# Display-Board_Rack-PDU_1_0.net
KiCad netlist of a schematic drawn in EAGLE
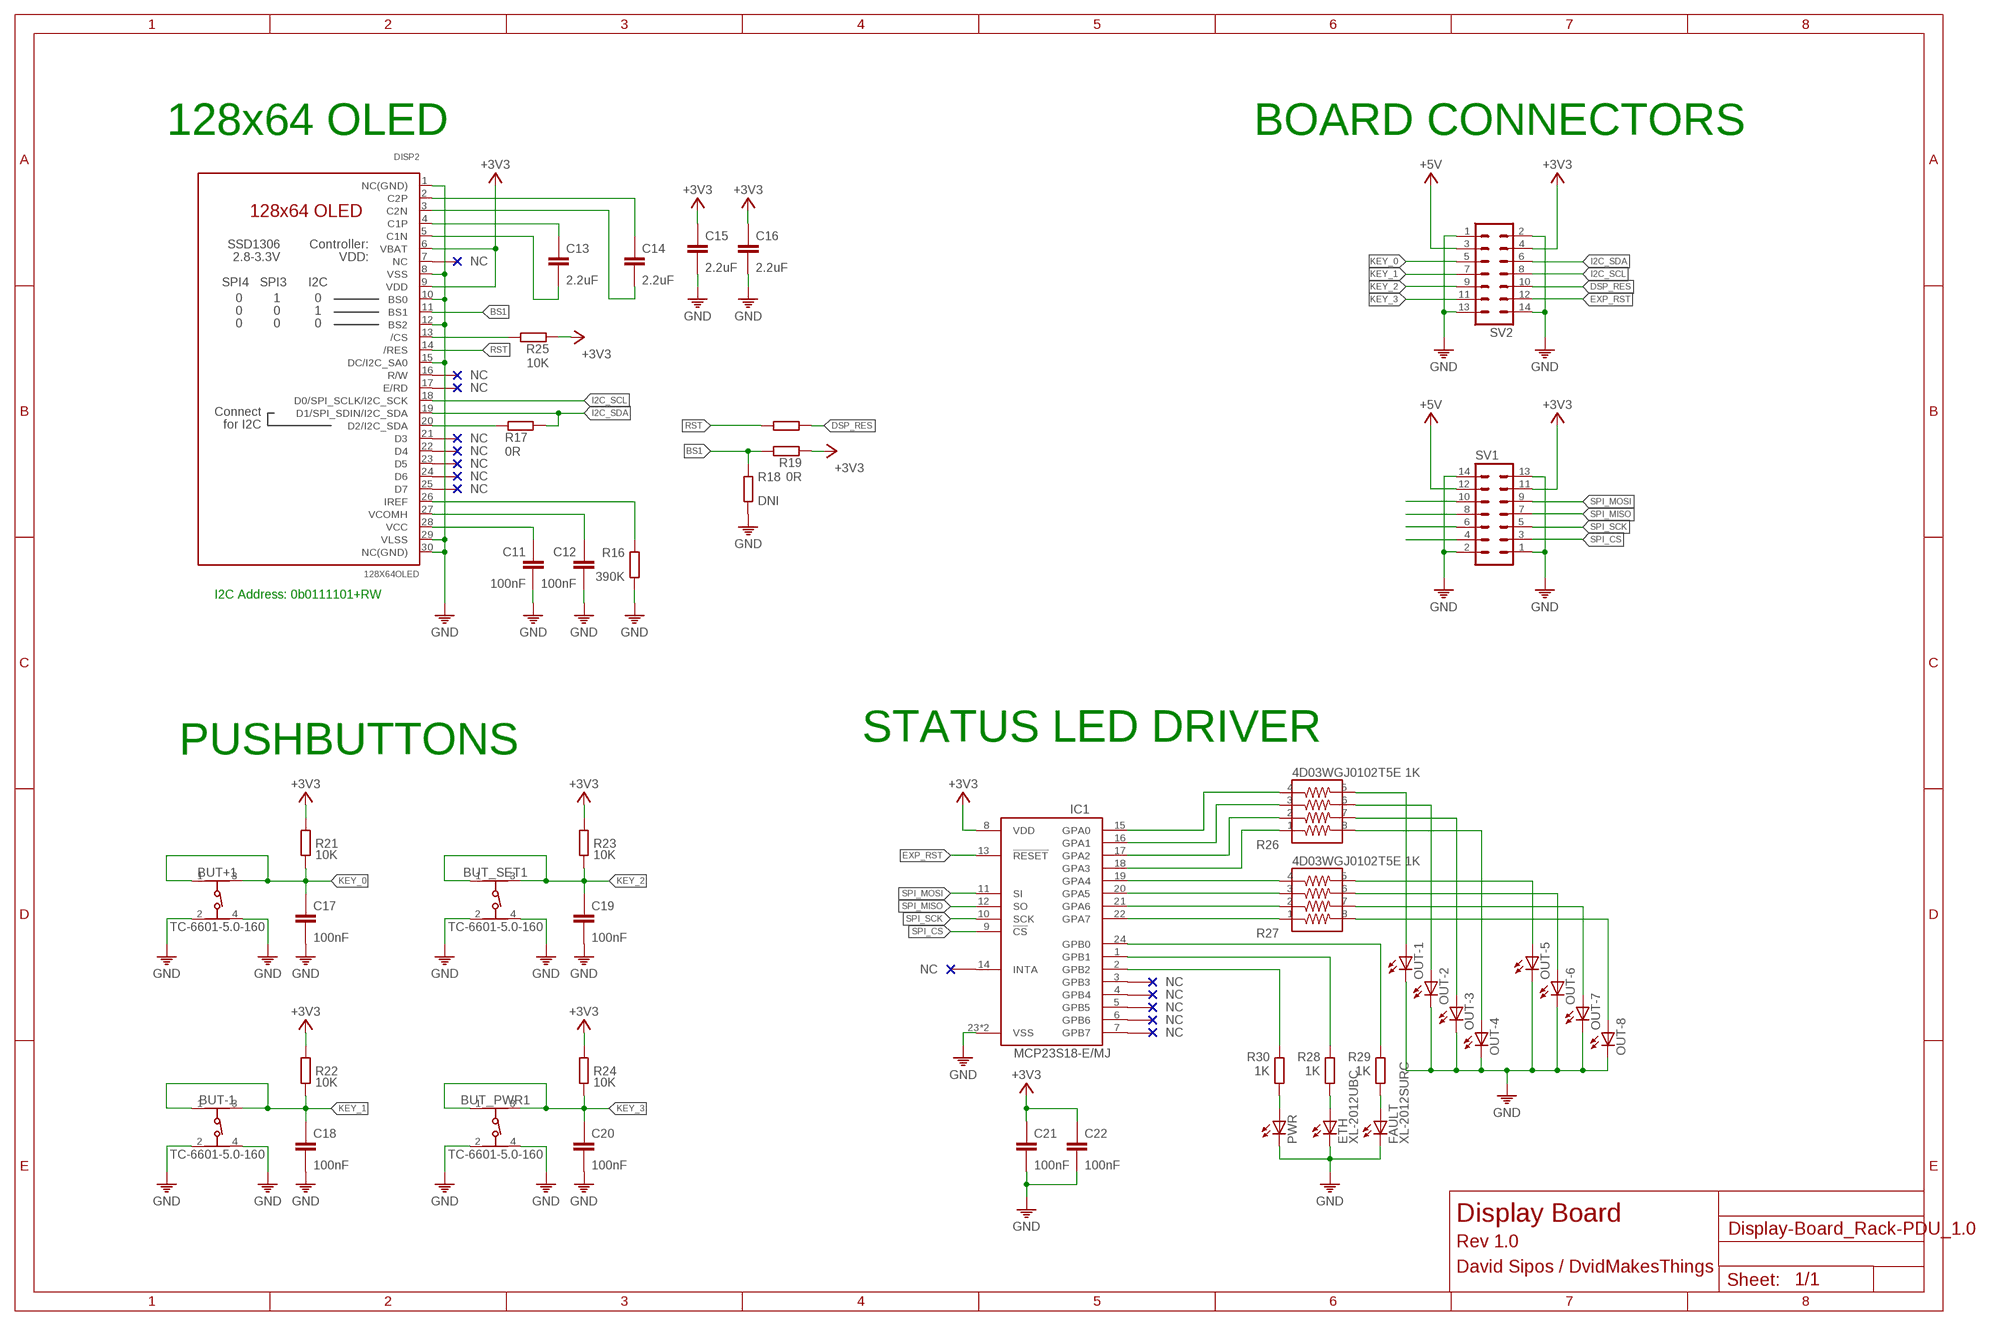
[diagram p0: schematic, sheet 1]

(export (version "E")
  (design (tool "Eeschema 10.0.6"))
  (components
    (comp (ref "BUT+1")
      (value "TC-6601-5.0-160")
      (footprint "eagle-import:430182043816")
      (libsource (lib "eagle-import") (part "430182043816"))
    )
    (comp (ref "BUT-1")
      (value "TC-6601-5.0-160")
      (footprint "eagle-import:430182043816")
      (libsource (lib "eagle-import") (part "430182043816"))
    )
    (comp (ref "BUT_PWR1")
      (value "TC-6601-5.0-160")
      (footprint "eagle-import:430182043816")
      (libsource (lib "eagle-import") (part "430182043816"))
    )
    (comp (ref "BUT_SET1")
      (value "TC-6601-5.0-160")
      (footprint "eagle-import:430182043816")
      (libsource (lib "eagle-import") (part "430182043816"))
    )
    (comp (ref "C11")
      (value "100nF")
      (footprint "eagle-import:0402")
      (libsource (lib "eagle-import") (part "C0402"))
    )
    (comp (ref "C12")
      (value "100nF")
      (footprint "eagle-import:0402")
      (libsource (lib "eagle-import") (part "C0402"))
    )
    (comp (ref "C13")
      (value "2.2uF")
      (footprint "eagle-import:0402")
      (libsource (lib "eagle-import") (part "C0402"))
    )
    (comp (ref "C14")
      (value "2.2uF")
      (footprint "eagle-import:0402")
      (libsource (lib "eagle-import") (part "C0402"))
    )
    (comp (ref "C15")
      (value "2.2uF")
      (footprint "eagle-import:0402")
      (libsource (lib "eagle-import") (part "C0402"))
    )
    (comp (ref "C16")
      (value "2.2uF")
      (footprint "eagle-import:0402")
      (libsource (lib "eagle-import") (part "C0402"))
    )
    (comp (ref "C17")
      (value "100nF")
      (footprint "eagle-import:0402")
      (libsource (lib "eagle-import") (part "C0402"))
    )
    (comp (ref "C18")
      (value "100nF")
      (footprint "eagle-import:0402")
      (libsource (lib "eagle-import") (part "C0402"))
    )
    (comp (ref "C19")
      (value "100nF")
      (footprint "eagle-import:0402")
      (libsource (lib "eagle-import") (part "C0402"))
    )
    (comp (ref "C20")
      (value "100nF")
      (footprint "eagle-import:0402")
      (libsource (lib "eagle-import") (part "C0402"))
    )
    (comp (ref "C21")
      (value "100nF")
      (footprint "eagle-import:0402")
      (libsource (lib "eagle-import") (part "C0402"))
    )
    (comp (ref "C22")
      (value "100nF")
      (footprint "eagle-import:0402")
      (libsource (lib "eagle-import") (part "C0402"))
    )
    (comp (ref "DISP2")
      (value "128X64OLED")
      (footprint "eagle-import:UG2864")
      (libsource (lib "eagle-import") (part "128X64OLED"))
    )
    (comp (ref "ETH")
      (value "XL-2012UBC")
      (footprint "eagle-import:CHIP-LED0805")
      (libsource (lib "eagle-import") (part "LEDCHIP-LED0805"))
    )
    (comp (ref "FAULT")
      (value "XL-2012SURC")
      (footprint "eagle-import:CHIP-LED0805")
      (libsource (lib "eagle-import") (part "LEDCHIP-LED0805"))
    )
    (comp (ref "IC1")
      (value "MCP23S18-E/MJ")
      (footprint "eagle-import:QFN50P400X400X100-25T265")
      (libsource (lib "eagle-import") (part "MCP23S18"))
    )
    (comp (ref "OUT-1")
      (value "LEDCHIP-LED0805")
      (footprint "eagle-import:CHIP-LED0805")
      (libsource (lib "eagle-import") (part "LEDCHIP-LED0805"))
    )
    (comp (ref "OUT-2")
      (value "LEDCHIP-LED0805")
      (footprint "eagle-import:CHIP-LED0805")
      (libsource (lib "eagle-import") (part "LEDCHIP-LED0805"))
    )
    (comp (ref "OUT-3")
      (value "LEDCHIP-LED0805")
      (footprint "eagle-import:CHIP-LED0805")
      (libsource (lib "eagle-import") (part "LEDCHIP-LED0805"))
    )
    (comp (ref "OUT-4")
      (value "LEDCHIP-LED0805")
      (footprint "eagle-import:CHIP-LED0805")
      (libsource (lib "eagle-import") (part "LEDCHIP-LED0805"))
    )
    (comp (ref "OUT-5")
      (value "LEDCHIP-LED0805")
      (footprint "eagle-import:CHIP-LED0805")
      (libsource (lib "eagle-import") (part "LEDCHIP-LED0805"))
    )
    (comp (ref "OUT-6")
      (value "LEDCHIP-LED0805")
      (footprint "eagle-import:CHIP-LED0805")
      (libsource (lib "eagle-import") (part "LEDCHIP-LED0805"))
    )
    (comp (ref "OUT-7")
      (value "LEDCHIP-LED0805")
      (footprint "eagle-import:CHIP-LED0805")
      (libsource (lib "eagle-import") (part "LEDCHIP-LED0805"))
    )
    (comp (ref "OUT-8")
      (value "LEDCHIP-LED0805")
      (footprint "eagle-import:CHIP-LED0805")
      (libsource (lib "eagle-import") (part "LEDCHIP-LED0805"))
    )
    (comp (ref "PWR")
      (value "LEDCHIP-LED0805")
      (footprint "eagle-import:CHIP-LED0805")
      (libsource (lib "eagle-import") (part "LEDCHIP-LED0805"))
    )
    (comp (ref "R16")
      (value "390K")
      (footprint "eagle-import:0402")
      (libsource (lib "eagle-import") (part "R0402"))
    )
    (comp (ref "R17")
      (value "0R")
      (footprint "eagle-import:0402")
      (libsource (lib "eagle-import") (part "R0402"))
    )
    (comp (ref "R18")
      (value "DNI")
      (footprint "eagle-import:0402")
      (libsource (lib "eagle-import") (part "R0402"))
    )
    (comp (ref "R19")
      (value "0R")
      (footprint "eagle-import:0402")
      (libsource (lib "eagle-import") (part "R0402"))
    )
    (comp (ref "R20")
      (value "0R")
      (footprint "eagle-import:0402")
      (libsource (lib "eagle-import") (part "R0402"))
    )
    (comp (ref "R21")
      (value "10K")
      (footprint "eagle-import:0402")
      (libsource (lib "eagle-import") (part "R0402"))
    )
    (comp (ref "R22")
      (value "10K")
      (footprint "eagle-import:0402")
      (libsource (lib "eagle-import") (part "R0402"))
    )
    (comp (ref "R23")
      (value "10K")
      (footprint "eagle-import:0402")
      (libsource (lib "eagle-import") (part "R0402"))
    )
    (comp (ref "R24")
      (value "10K")
      (footprint "eagle-import:0402")
      (libsource (lib "eagle-import") (part "R0402"))
    )
    (comp (ref "R25")
      (value "10K")
      (footprint "eagle-import:0402")
      (libsource (lib "eagle-import") (part "R0402"))
    )
    (comp (ref "R26")
      (value "4D03WGJ0102T5E 1K")
      (footprint "eagle-import:742C083103JP")
      (fields
        (field (name "MANUFACTURER") "CTS Resistor Products")
        (field (name "MPN") "742C083103JP")
        (field (name "CREATED_BY") "PCBLayout.com")
      )
      (libsource (lib "eagle-import") (part "742C083103JP"))
    )
    (comp (ref "R27")
      (value "4D03WGJ0102T5E 1K")
      (footprint "eagle-import:742C083103JP")
      (fields
        (field (name "MANUFACTURER") "CTS Resistor Products")
        (field (name "MPN") "742C083103JP")
        (field (name "CREATED_BY") "PCBLayout.com")
      )
      (libsource (lib "eagle-import") (part "742C083103JP"))
    )
    (comp (ref "R28")
      (value "1K")
      (footprint "eagle-import:0402")
      (libsource (lib "eagle-import") (part "R0402"))
    )
    (comp (ref "R29")
      (value "1K")
      (footprint "eagle-import:0402")
      (libsource (lib "eagle-import") (part "R0402"))
    )
    (comp (ref "R30")
      (value "1K")
      (footprint "eagle-import:0402")
      (libsource (lib "eagle-import") (part "R0402"))
    )
    (comp (ref "SV1")
      (value "MA07-2W")
      (footprint "eagle-import:MA07-2W")
      (libsource (lib "eagle-import") (part "MA07-2W"))
    )
    (comp (ref "SV2")
      (value "MA07-2W")
      (footprint "eagle-import:MA07-2W")
      (libsource (lib "eagle-import") (part "MA07-2W"))
    )
  )
  (nets
    (net (code "1") (name "+3V3") (class "Default")
      (node (ref "C15") (pin "1") (pinfunction "1_1") (pintype "passive"))
      (node (ref "C16") (pin "1") (pinfunction "1_1") (pintype "passive"))
      (node (ref "C21") (pin "1") (pinfunction "1_1") (pintype "passive"))
      (node (ref "C22") (pin "1") (pinfunction "1_1") (pintype "passive"))
      (node (ref "DISP2") (pin "6") (pinfunction "VBAT_6") (pintype "input"))
      (node (ref "DISP2") (pin "9") (pinfunction "VDD_9") (pintype "power_in"))
      (node (ref "IC1") (pin "8") (pinfunction "VDD_8") (pintype "power_in"))
      (node (ref "R19") (pin "1") (pinfunction "1_1") (pintype "passive"))
      (node (ref "R21") (pin "1") (pinfunction "1_1") (pintype "passive"))
      (node (ref "R22") (pin "1") (pinfunction "1_1") (pintype "passive"))
      (node (ref "R23") (pin "1") (pinfunction "1_1") (pintype "passive"))
      (node (ref "R24") (pin "1") (pinfunction "1_1") (pintype "passive"))
      (node (ref "R25") (pin "1") (pinfunction "1_1") (pintype "passive"))
      (node (ref "SV1") (pin "11") (pinfunction "11_11") (pintype "passive"))
      (node (ref "SV2") (pin "4") (pinfunction "4_4") (pintype "passive"))
    )
    (net (code "2") (name "+5V") (class "Default")
      (node (ref "SV1") (pin "12") (pinfunction "12_12") (pintype "passive"))
      (node (ref "SV2") (pin "3") (pinfunction "3_3") (pintype "passive"))
    )
    (net (code "3") (name "BS1") (class "Default")
      (node (ref "DISP2") (pin "11") (pinfunction "BS1_11") (pintype "input"))
      (node (ref "R18") (pin "1") (pinfunction "1_1") (pintype "passive"))
      (node (ref "R19") (pin "2") (pinfunction "2_2") (pintype "passive"))
    )
    (net (code "4") (name "DSP_RES") (class "Default")
      (node (ref "R20") (pin "2") (pinfunction "2_2") (pintype "passive"))
      (node (ref "SV2") (pin "10") (pinfunction "10_10") (pintype "passive"))
    )
    (net (code "5") (name "EXP_RST") (class "Default")
      (node (ref "IC1") (pin "13") (pinfunction "~{RESET}_13") (pintype "input"))
      (node (ref "SV2") (pin "12") (pinfunction "12_12") (pintype "passive"))
    )
    (net (code "6") (name "GND") (class "Default")
      (node (ref "BUT+1") (pin "2") (pinfunction "2_2") (pintype "passive"))
      (node (ref "BUT+1") (pin "4") (pinfunction "4_4") (pintype "passive"))
      (node (ref "BUT-1") (pin "2") (pinfunction "2_2") (pintype "passive"))
      (node (ref "BUT-1") (pin "4") (pinfunction "4_4") (pintype "passive"))
      (node (ref "BUT_PWR1") (pin "2") (pinfunction "2_2") (pintype "passive"))
      (node (ref "BUT_PWR1") (pin "4") (pinfunction "4_4") (pintype "passive"))
      (node (ref "BUT_SET1") (pin "2") (pinfunction "2_2") (pintype "passive"))
      (node (ref "BUT_SET1") (pin "4") (pinfunction "4_4") (pintype "passive"))
      (node (ref "C11") (pin "2") (pinfunction "2_2") (pintype "passive"))
      (node (ref "C12") (pin "2") (pinfunction "2_2") (pintype "passive"))
      (node (ref "C15") (pin "2") (pinfunction "2_2") (pintype "passive"))
      (node (ref "C16") (pin "2") (pinfunction "2_2") (pintype "passive"))
      (node (ref "C17") (pin "2") (pinfunction "2_2") (pintype "passive"))
      (node (ref "C18") (pin "2") (pinfunction "2_2") (pintype "passive"))
      (node (ref "C19") (pin "2") (pinfunction "2_2") (pintype "passive"))
      (node (ref "C20") (pin "2") (pinfunction "2_2") (pintype "passive"))
      (node (ref "C21") (pin "2") (pinfunction "2_2") (pintype "passive"))
      (node (ref "C22") (pin "2") (pinfunction "2_2") (pintype "passive"))
      (node (ref "DISP2") (pin "1") (pinfunction "NC(GND)_1") (pintype "input"))
      (node (ref "DISP2") (pin "10") (pinfunction "BS0_10") (pintype "input"))
      (node (ref "DISP2") (pin "12") (pinfunction "BS2_12") (pintype "input"))
      (node (ref "DISP2") (pin "15") (pinfunction "DC/I2C_SA0_15") (pintype "input"))
      (node (ref "DISP2") (pin "29") (pinfunction "VLSS_29") (pintype "power_in"))
      (node (ref "DISP2") (pin "30") (pinfunction "NC(GND)_30") (pintype "input"))
      (node (ref "DISP2") (pin "8") (pinfunction "VSS_8") (pintype "power_in"))
      (node (ref "ETH") (pin "C") (pinfunction "C_C") (pintype "passive"))
      (node (ref "FAULT") (pin "C") (pinfunction "C_C") (pintype "passive"))
      (node (ref "IC1") (pin "23") (pinfunction "VSS_23") (pintype "power_in"))
      (node (ref "IC1") (pin "25") (pinfunction "VSS_25") (pintype "power_in"))
      (node (ref "OUT-1") (pin "C") (pinfunction "C_C") (pintype "passive"))
      (node (ref "OUT-2") (pin "C") (pinfunction "C_C") (pintype "passive"))
      (node (ref "OUT-3") (pin "C") (pinfunction "C_C") (pintype "passive"))
      (node (ref "OUT-4") (pin "C") (pinfunction "C_C") (pintype "passive"))
      (node (ref "OUT-5") (pin "C") (pinfunction "C_C") (pintype "passive"))
      (node (ref "OUT-6") (pin "C") (pinfunction "C_C") (pintype "passive"))
      (node (ref "OUT-7") (pin "C") (pinfunction "C_C") (pintype "passive"))
      (node (ref "OUT-8") (pin "C") (pinfunction "C_C") (pintype "passive"))
      (node (ref "PWR") (pin "C") (pinfunction "C_C") (pintype "passive"))
      (node (ref "R16") (pin "2") (pinfunction "2_2") (pintype "passive"))
      (node (ref "R18") (pin "2") (pinfunction "2_2") (pintype "passive"))
      (node (ref "SV1") (pin "1") (pinfunction "1_1") (pintype "passive"))
      (node (ref "SV1") (pin "13") (pinfunction "13_13") (pintype "passive"))
      (node (ref "SV1") (pin "14") (pinfunction "14_14") (pintype "passive"))
      (node (ref "SV1") (pin "2") (pinfunction "2_2") (pintype "passive"))
      (node (ref "SV2") (pin "1") (pinfunction "1_1") (pintype "passive"))
      (node (ref "SV2") (pin "13") (pinfunction "13_13") (pintype "passive"))
      (node (ref "SV2") (pin "14") (pinfunction "14_14") (pintype "passive"))
      (node (ref "SV2") (pin "2") (pinfunction "2_2") (pintype "passive"))
    )
    (net (code "7") (name "I2C_SCL") (class "Default")
      (node (ref "DISP2") (pin "18") (pinfunction "D0/SPI_SCLK/I2C_SCK_18") (pintype "bidirectional"))
      (node (ref "SV2") (pin "8") (pinfunction "8_8") (pintype "passive"))
    )
    (net (code "8") (name "I2C_SDA") (class "Default")
      (node (ref "DISP2") (pin "19") (pinfunction "D1/SPI_SDIN/I2C_SDA_19") (pintype "bidirectional"))
      (node (ref "R17") (pin "2") (pinfunction "2_2") (pintype "passive"))
      (node (ref "SV2") (pin "6") (pinfunction "6_6") (pintype "passive"))
    )
    (net (code "9") (name "KEY_0") (class "Default")
      (node (ref "BUT+1") (pin "1") (pinfunction "1_1") (pintype "passive"))
      (node (ref "BUT+1") (pin "3") (pinfunction "3_3") (pintype "passive"))
      (node (ref "C17") (pin "1") (pinfunction "1_1") (pintype "passive"))
      (node (ref "R21") (pin "2") (pinfunction "2_2") (pintype "passive"))
      (node (ref "SV2") (pin "5") (pinfunction "5_5") (pintype "passive"))
    )
    (net (code "10") (name "KEY_1") (class "Default")
      (node (ref "BUT-1") (pin "1") (pinfunction "1_1") (pintype "passive"))
      (node (ref "BUT-1") (pin "3") (pinfunction "3_3") (pintype "passive"))
      (node (ref "C18") (pin "1") (pinfunction "1_1") (pintype "passive"))
      (node (ref "R22") (pin "2") (pinfunction "2_2") (pintype "passive"))
      (node (ref "SV2") (pin "7") (pinfunction "7_7") (pintype "passive"))
    )
    (net (code "11") (name "KEY_2") (class "Default")
      (node (ref "BUT_SET1") (pin "1") (pinfunction "1_1") (pintype "passive"))
      (node (ref "BUT_SET1") (pin "3") (pinfunction "3_3") (pintype "passive"))
      (node (ref "C19") (pin "1") (pinfunction "1_1") (pintype "passive"))
      (node (ref "R23") (pin "2") (pinfunction "2_2") (pintype "passive"))
      (node (ref "SV2") (pin "9") (pinfunction "9_9") (pintype "passive"))
    )
    (net (code "12") (name "KEY_3") (class "Default")
      (node (ref "BUT_PWR1") (pin "1") (pinfunction "1_1") (pintype "passive"))
      (node (ref "BUT_PWR1") (pin "3") (pinfunction "3_3") (pintype "passive"))
      (node (ref "C20") (pin "1") (pinfunction "1_1") (pintype "passive"))
      (node (ref "R24") (pin "2") (pinfunction "2_2") (pintype "passive"))
      (node (ref "SV2") (pin "11") (pinfunction "11_11") (pintype "passive"))
    )
    (net (code "13") (name "Net-(DISP2-C1N)") (class "Default")
      (node (ref "C13") (pin "2") (pinfunction "2_2") (pintype "passive"))
      (node (ref "DISP2") (pin "5") (pinfunction "C1N_5") (pintype "input"))
    )
    (net (code "14") (name "Net-(DISP2-C1P)") (class "Default")
      (node (ref "C13") (pin "1") (pinfunction "1_1") (pintype "passive"))
      (node (ref "DISP2") (pin "4") (pinfunction "C1P_4") (pintype "input"))
    )
    (net (code "15") (name "Net-(DISP2-C2N)") (class "Default")
      (node (ref "C14") (pin "2") (pinfunction "2_2") (pintype "passive"))
      (node (ref "DISP2") (pin "3") (pinfunction "C2N_3") (pintype "input"))
    )
    (net (code "16") (name "Net-(DISP2-C2P)") (class "Default")
      (node (ref "C14") (pin "1") (pinfunction "1_1") (pintype "passive"))
      (node (ref "DISP2") (pin "2") (pinfunction "C2P_2") (pintype "input"))
    )
    (net (code "17") (name "Net-(DISP2-D2{slash}I2C_SDA)") (class "Default")
      (node (ref "DISP2") (pin "20") (pinfunction "D2/I2C_SDA_20") (pintype "bidirectional"))
      (node (ref "R17") (pin "1") (pinfunction "1_1") (pintype "passive"))
    )
    (net (code "18") (name "Net-(DISP2-IREF)") (class "Default")
      (node (ref "DISP2") (pin "26") (pinfunction "IREF_26") (pintype "input"))
      (node (ref "R16") (pin "1") (pinfunction "1_1") (pintype "passive"))
    )
    (net (code "19") (name "Net-(DISP2-VCC)") (class "Default")
      (node (ref "C11") (pin "1") (pinfunction "1_1") (pintype "passive"))
      (node (ref "DISP2") (pin "28") (pinfunction "VCC_28") (pintype "power_in"))
    )
    (net (code "20") (name "Net-(DISP2-VCOMH)") (class "Default")
      (node (ref "C12") (pin "1") (pinfunction "1_1") (pintype "passive"))
      (node (ref "DISP2") (pin "27") (pinfunction "VCOMH_27") (pintype "output"))
    )
    (net (code "21") (name "Net-(DISP2-{slash}CS)") (class "Default")
      (node (ref "DISP2") (pin "13") (pinfunction "/CS_13") (pintype "input"))
      (node (ref "R25") (pin "2") (pinfunction "2_2") (pintype "passive"))
    )
    (net (code "22") (name "Net-(ETH-PadA)") (class "Default")
      (node (ref "ETH") (pin "A") (pinfunction "A_A") (pintype "passive"))
      (node (ref "R28") (pin "2") (pinfunction "2_2") (pintype "passive"))
    )
    (net (code "23") (name "Net-(FAULT-PadA)") (class "Default")
      (node (ref "FAULT") (pin "A") (pinfunction "A_A") (pintype "passive"))
      (node (ref "R29") (pin "2") (pinfunction "2_2") (pintype "passive"))
    )
    (net (code "24") (name "Net-(IC1-GPA0)") (class "Default")
      (node (ref "IC1") (pin "15") (pinfunction "GPA0_15") (pintype "bidirectional"))
      (node (ref "R26") (pin "4") (pinfunction "4_4") (pintype "passive"))
    )
    (net (code "25") (name "Net-(IC1-GPA1)") (class "Default")
      (node (ref "IC1") (pin "16") (pinfunction "GPA1_16") (pintype "bidirectional"))
      (node (ref "R26") (pin "3") (pinfunction "3_3") (pintype "passive"))
    )
    (net (code "26") (name "Net-(IC1-GPA2)") (class "Default")
      (node (ref "IC1") (pin "17") (pinfunction "GPA2_17") (pintype "bidirectional"))
      (node (ref "R26") (pin "2") (pinfunction "2_2") (pintype "passive"))
    )
    (net (code "27") (name "Net-(IC1-GPA3)") (class "Default")
      (node (ref "IC1") (pin "18") (pinfunction "GPA3_18") (pintype "bidirectional"))
      (node (ref "R26") (pin "1") (pinfunction "1_1") (pintype "passive"))
    )
    (net (code "28") (name "Net-(IC1-GPA4)") (class "Default")
      (node (ref "IC1") (pin "19") (pinfunction "GPA4_19") (pintype "bidirectional"))
      (node (ref "R27") (pin "4") (pinfunction "4_4") (pintype "passive"))
    )
    (net (code "29") (name "Net-(IC1-GPA5)") (class "Default")
      (node (ref "IC1") (pin "20") (pinfunction "GPA5_20") (pintype "bidirectional"))
      (node (ref "R27") (pin "3") (pinfunction "3_3") (pintype "passive"))
    )
    (net (code "30") (name "Net-(IC1-GPA6)") (class "Default")
      (node (ref "IC1") (pin "21") (pinfunction "GPA6_21") (pintype "bidirectional"))
      (node (ref "R27") (pin "2") (pinfunction "2_2") (pintype "passive"))
    )
    (net (code "31") (name "Net-(IC1-GPA7)") (class "Default")
      (node (ref "IC1") (pin "22") (pinfunction "GPA7_22") (pintype "bidirectional"))
      (node (ref "R27") (pin "1") (pinfunction "1_1") (pintype "passive"))
    )
    (net (code "32") (name "Net-(IC1-GPB0)") (class "Default")
      (node (ref "IC1") (pin "24") (pinfunction "GPB0_24") (pintype "bidirectional"))
      (node (ref "R29") (pin "1") (pinfunction "1_1") (pintype "passive"))
    )
    (net (code "33") (name "Net-(IC1-GPB1)") (class "Default")
      (node (ref "IC1") (pin "1") (pinfunction "GPB1_1") (pintype "bidirectional"))
      (node (ref "R28") (pin "1") (pinfunction "1_1") (pintype "passive"))
    )
    (net (code "34") (name "Net-(IC1-GPB2)") (class "Default")
      (node (ref "IC1") (pin "2") (pinfunction "GPB2_2") (pintype "bidirectional"))
      (node (ref "R30") (pin "1") (pinfunction "1_1") (pintype "passive"))
    )
    (net (code "35") (name "Net-(OUT-1-PadA)") (class "Default")
      (node (ref "OUT-1") (pin "A") (pinfunction "A_A") (pintype "passive"))
      (node (ref "R26") (pin "5") (pinfunction "5_5") (pintype "passive"))
    )
    (net (code "36") (name "Net-(OUT-2-PadA)") (class "Default")
      (node (ref "OUT-2") (pin "A") (pinfunction "A_A") (pintype "passive"))
      (node (ref "R26") (pin "6") (pinfunction "6_6") (pintype "passive"))
    )
    (net (code "37") (name "Net-(OUT-3-PadA)") (class "Default")
      (node (ref "OUT-3") (pin "A") (pinfunction "A_A") (pintype "passive"))
      (node (ref "R26") (pin "7") (pinfunction "7_7") (pintype "passive"))
    )
    (net (code "38") (name "Net-(OUT-4-PadA)") (class "Default")
      (node (ref "OUT-4") (pin "A") (pinfunction "A_A") (pintype "passive"))
      (node (ref "R26") (pin "8") (pinfunction "8_8") (pintype "passive"))
    )
    (net (code "39") (name "Net-(OUT-5-PadA)") (class "Default")
      (node (ref "OUT-5") (pin "A") (pinfunction "A_A") (pintype "passive"))
      (node (ref "R27") (pin "5") (pinfunction "5_5") (pintype "passive"))
    )
    (net (code "40") (name "Net-(OUT-6-PadA)") (class "Default")
      (node (ref "OUT-6") (pin "A") (pinfunction "A_A") (pintype "passive"))
      (node (ref "R27") (pin "6") (pinfunction "6_6") (pintype "passive"))
    )
    (net (code "41") (name "Net-(OUT-7-PadA)") (class "Default")
      (node (ref "OUT-7") (pin "A") (pinfunction "A_A") (pintype "passive"))
      (node (ref "R27") (pin "7") (pinfunction "7_7") (pintype "passive"))
    )
    (net (code "42") (name "Net-(OUT-8-PadA)") (class "Default")
      (node (ref "OUT-8") (pin "A") (pinfunction "A_A") (pintype "passive"))
      (node (ref "R27") (pin "8") (pinfunction "8_8") (pintype "passive"))
    )
    (net (code "43") (name "Net-(PWR-PadA)") (class "Default")
      (node (ref "PWR") (pin "A") (pinfunction "A_A") (pintype "passive"))
      (node (ref "R30") (pin "2") (pinfunction "2_2") (pintype "passive"))
    )
    (net (code "44") (name "RST") (class "Default")
      (node (ref "DISP2") (pin "14") (pinfunction "/RES_14") (pintype "input"))
      (node (ref "R20") (pin "1") (pinfunction "1_1") (pintype "passive"))
    )
    (net (code "45") (name "SPI_CS") (class "Default")
      (node (ref "IC1") (pin "9") (pinfunction "~{CS}_9") (pintype "input"))
      (node (ref "SV1") (pin "3") (pinfunction "3_3") (pintype "passive"))
    )
    (net (code "46") (name "SPI_MISO") (class "Default")
      (node (ref "IC1") (pin "12") (pinfunction "SO_12") (pintype "output"))
      (node (ref "SV1") (pin "7") (pinfunction "7_7") (pintype "passive"))
    )
    (net (code "47") (name "SPI_MOSI") (class "Default")
      (node (ref "IC1") (pin "11") (pinfunction "SI_11") (pintype "input"))
      (node (ref "SV1") (pin "9") (pinfunction "9_9") (pintype "passive"))
    )
    (net (code "48") (name "SPI_SCK") (class "Default")
      (node (ref "IC1") (pin "10") (pinfunction "SCK_10") (pintype "input"))
      (node (ref "SV1") (pin "5") (pinfunction "5_5") (pintype "passive"))
    )
    (net (code "49") (name "unconnected-(DISP2-D3-Pad21)") (class "Default")
      (node (ref "DISP2") (pin "21") (pinfunction "D3_21") (pintype "bidirectional"))
    )
    (net (code "50") (name "unconnected-(DISP2-D4-Pad22)") (class "Default")
      (node (ref "DISP2") (pin "22") (pinfunction "D4_22") (pintype "bidirectional"))
    )
    (net (code "51") (name "unconnected-(DISP2-D5-Pad23)") (class "Default")
      (node (ref "DISP2") (pin "23") (pinfunction "D5_23") (pintype "bidirectional"))
    )
    (net (code "52") (name "unconnected-(DISP2-D6-Pad24)") (class "Default")
      (node (ref "DISP2") (pin "24") (pinfunction "D6_24") (pintype "bidirectional"))
    )
    (net (code "53") (name "unconnected-(DISP2-D7-Pad25)") (class "Default")
      (node (ref "DISP2") (pin "25") (pinfunction "D7_25") (pintype "bidirectional"))
    )
    (net (code "54") (name "unconnected-(DISP2-E{slash}RD-Pad17)") (class "Default")
      (node (ref "DISP2") (pin "17") (pinfunction "E/RD_17") (pintype "input"))
    )
    (net (code "55") (name "unconnected-(DISP2-NC-Pad7)") (class "Default")
      (node (ref "DISP2") (pin "7") (pinfunction "NC_7") (pintype "no_connect"))
    )
    (net (code "56") (name "unconnected-(DISP2-R{slash}W-Pad16)") (class "Default")
      (node (ref "DISP2") (pin "16") (pinfunction "R/W_16") (pintype "input"))
    )
    (net (code "57") (name "unconnected-(IC1-GPB3-Pad3)") (class "Default")
      (node (ref "IC1") (pin "3") (pinfunction "GPB3_3") (pintype "bidirectional"))
    )
    (net (code "58") (name "unconnected-(IC1-GPB4-Pad4)") (class "Default")
      (node (ref "IC1") (pin "4") (pinfunction "GPB4_4") (pintype "bidirectional"))
    )
    (net (code "59") (name "unconnected-(IC1-GPB5-Pad5)") (class "Default")
      (node (ref "IC1") (pin "5") (pinfunction "GPB5_5") (pintype "bidirectional"))
    )
    (net (code "60") (name "unconnected-(IC1-GPB6-Pad6)") (class "Default")
      (node (ref "IC1") (pin "6") (pinfunction "GPB6_6") (pintype "bidirectional"))
    )
    (net (code "61") (name "unconnected-(IC1-GPB7-Pad7)") (class "Default")
      (node (ref "IC1") (pin "7") (pinfunction "GPB7_7") (pintype "bidirectional"))
    )
    (net (code "62") (name "unconnected-(IC1-INTA-Pad14)") (class "Default")
      (node (ref "IC1") (pin "14") (pinfunction "INTA_14") (pintype "output"))
    )
    (net (code "63") (name "unconnected-(SV1-Pad4)") (class "Default")
      (node (ref "SV1") (pin "4") (pinfunction "4_4") (pintype "passive"))
    )
    (net (code "64") (name "unconnected-(SV1-Pad6)") (class "Default")
      (node (ref "SV1") (pin "6") (pinfunction "6_6") (pintype "passive"))
    )
    (net (code "65") (name "unconnected-(SV1-Pad8)") (class "Default")
      (node (ref "SV1") (pin "8") (pinfunction "8_8") (pintype "passive"))
    )
    (net (code "66") (name "unconnected-(SV1-Pad10)") (class "Default")
      (node (ref "SV1") (pin "10") (pinfunction "10_10") (pintype "passive"))
    )
  )
)
